# 03_Codec.net
KiCad netlist of a schematic drawn in Altium Designer
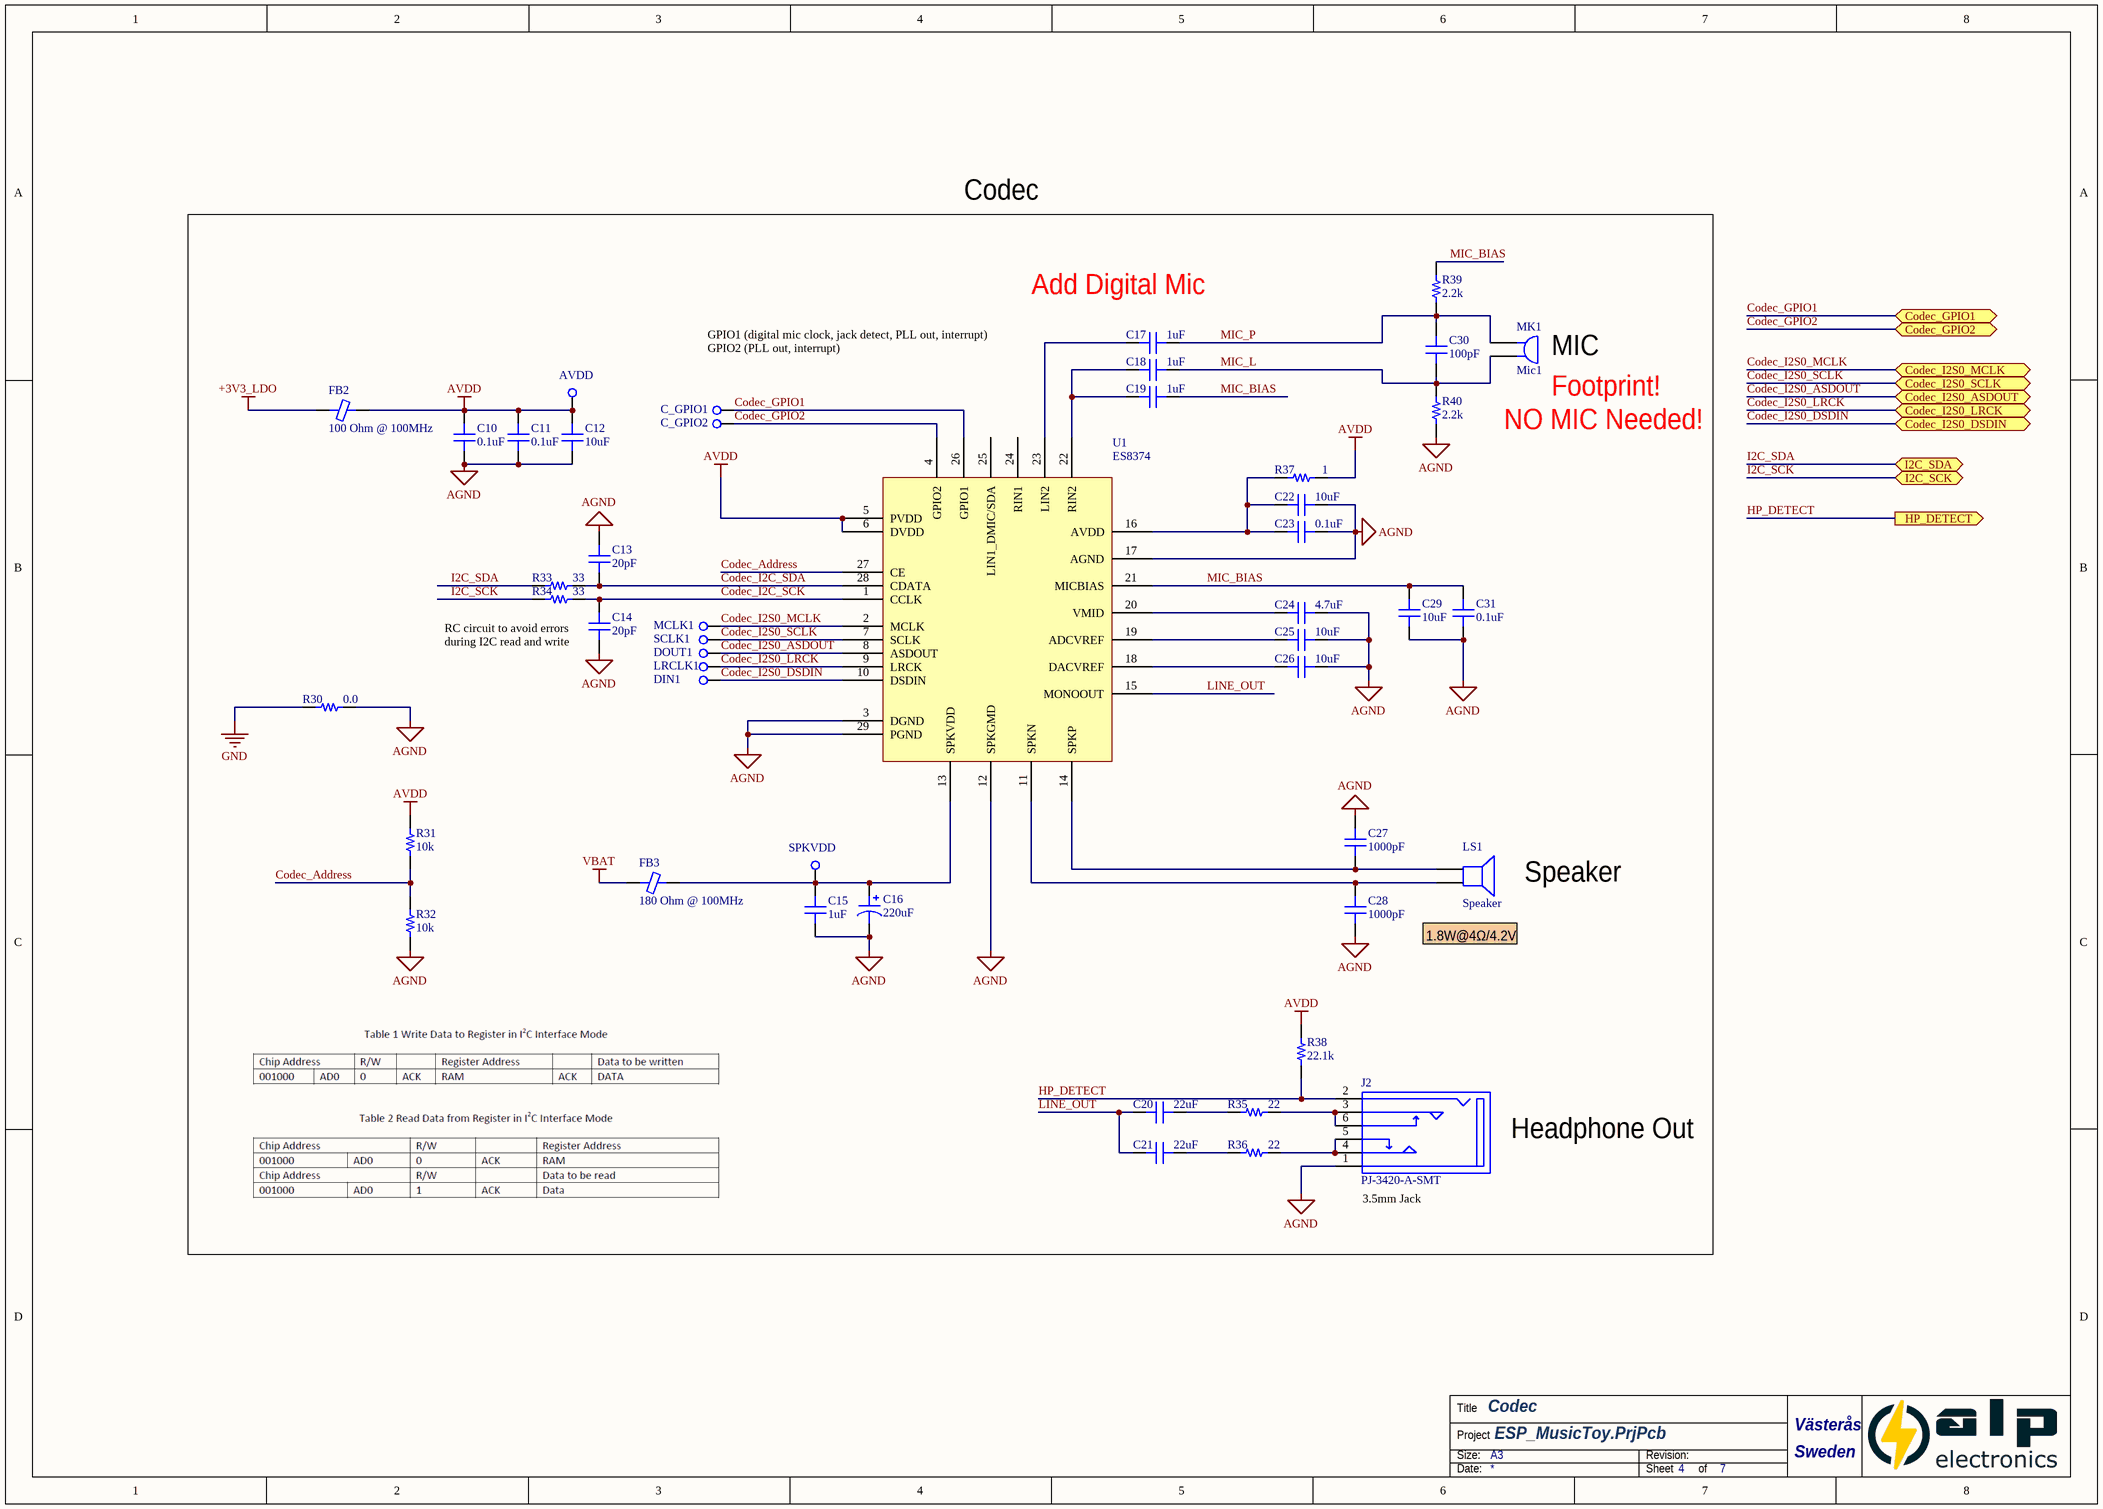
[diagram p0: [03] Codec.SchDoc]

(export (version "E")
  (design (tool "Eeschema 10.0.6"))
  (components
    (comp (ref "AVDD")
      (value "RCT-0C")
      (footprint "3D FootPrint_Backup:0.5mm-TestPad")
      (description "0805 PROBE PAD")
      (fields (field (name "MANUFACTURER") "TE Connectivity AMP Connectors"))
      (libsource (lib "Celestial Library Database") (part "Test Point"))
    )
    (comp (ref "C10")
      (value "0.1uF")
      (footprint "CAP 0603/1608")
      (description "CAP CER 0.1UF 16V X7R 0603")
      (fields (field (name "PART NUMBER") "CC0603KPX7R7BB104") (field (name "MANUFACTURER") "Yageo"))
      (libsource (lib "Celestial Library Database") (part "Capacitor"))
    )
    (comp (ref "C11")
      (value "0.1uF")
      (footprint "CAP 0603/1608")
      (description "CAP CER 0.1UF 16V X7R 0603")
      (fields (field (name "PART NUMBER") "CC0603KPX7R7BB104") (field (name "MANUFACTURER") "Yageo"))
      (libsource (lib "Celestial Library Database") (part "Capacitor"))
    )
    (comp (ref "C12")
      (value "10uF")
      (footprint "CAP 0603/1608")
      (description "CAP CER 10UF 10V X5R 0603")
      (fields
        (field (name "PART NUMBER") "C1608X5R1A106M080AC")
        (field (name "MANUFACTURER") "TDK Corporation")
      )
      (libsource (lib "Celestial Library Database") (part "Capacitor"))
    )
    (comp (ref "C13")
      (value "20pF")
      (footprint "CAP 0402/1005")
      (description "CAP CER 20PF 25V NP0 0402")
      (fields
        (field (name "PART NUMBER") "GRM1555C1E200JA01D")
        (field (name "MANUFACTURER") "Murata Electronics North America")
      )
      (libsource (lib "Celestial Library Database") (part "Capacitor"))
    )
    (comp (ref "C14")
      (value "20pF")
      (footprint "CAP 0402/1005")
      (description "CAP CER 20PF 25V NP0 0402")
      (fields
        (field (name "PART NUMBER") "GRM1555C1E200JA01D")
        (field (name "MANUFACTURER") "Murata Electronics North America")
      )
      (libsource (lib "Celestial Library Database") (part "Capacitor"))
    )
    (comp (ref "C15")
      (value "1uF")
      (footprint "CAP 0603/1608")
      (description "CAP CER 1UF 10V X7R 0603")
      (fields
        (field (name "PART NUMBER") "CGB3B1X7R1A105K055AC")
        (field (name "MANUFACTURER") "TDK Corporation")
      )
      (libsource (lib "Celestial Library Database") (part "Capacitor"))
    )
    (comp (ref "C16")
      (value "220uF")
      (footprint "CAP ALUM 6.6MM")
      (description "CAP ALUM 220UF 20% 16V SMD")
      (fields
        (field (name "PART NUMBER") "EEE-1CA221XP")
        (field (name "MANUFACTURER") "Panasonic Electronic Components")
      )
      (libsource (lib "Celestial Library Database") (part "Polarised Capacitor"))
    )
    (comp (ref "C17")
      (value "1uF")
      (footprint "CAP 0603/1608")
      (description "CAP CER 1UF 10V X7R 0603")
      (fields
        (field (name "PART NUMBER") "CGB3B1X7R1A105K055AC")
        (field (name "MANUFACTURER") "TDK Corporation")
      )
      (libsource (lib "Celestial Library Database") (part "Capacitor"))
    )
    (comp (ref "C18")
      (value "1uF")
      (footprint "CAP 0603/1608")
      (description "CAP CER 1UF 10V X7R 0603")
      (fields
        (field (name "PART NUMBER") "CGB3B1X7R1A105K055AC")
        (field (name "MANUFACTURER") "TDK Corporation")
      )
      (libsource (lib "Celestial Library Database") (part "Capacitor"))
    )
    (comp (ref "C19")
      (value "1uF")
      (footprint "CAP 0603/1608")
      (description "CAP CER 1UF 10V X7R 0603")
      (fields
        (field (name "PART NUMBER") "CGB3B1X7R1A105K055AC")
        (field (name "MANUFACTURER") "TDK Corporation")
      )
      (libsource (lib "Celestial Library Database") (part "Capacitor"))
    )
    (comp (ref "C20")
      (value "22uF")
      (footprint "CAP 0603/1608")
      (description "CAP CER 22UF 10V X5R 0603")
      (fields
        (field (name "PART NUMBER") "C1608X5R1A226M080AC")
        (field (name "MANUFACTURER") "TDK Corporation")
      )
      (libsource (lib "Celestial Library Database") (part "Capacitor"))
    )
    (comp (ref "C21")
      (value "22uF")
      (footprint "CAP 0603/1608")
      (description "CAP CER 22UF 10V X5R 0603")
      (fields
        (field (name "PART NUMBER") "C1608X5R1A226M080AC")
        (field (name "MANUFACTURER") "TDK Corporation")
      )
      (libsource (lib "Celestial Library Database") (part "Capacitor"))
    )
    (comp (ref "C22")
      (value "10uF")
      (footprint "CAP 0603/1608")
      (description "CAP CER 10UF 10V X5R 0603")
      (fields
        (field (name "PART NUMBER") "C1608X5R1A106M080AC")
        (field (name "MANUFACTURER") "TDK Corporation")
      )
      (libsource (lib "Celestial Library Database") (part "Capacitor"))
    )
    (comp (ref "C23")
      (value "0.1uF")
      (footprint "CAP 0603/1608")
      (description "CAP CER 0.1UF 16V X7R 0603")
      (fields (field (name "PART NUMBER") "CC0603KPX7R7BB104") (field (name "MANUFACTURER") "Yageo"))
      (libsource (lib "Celestial Library Database") (part "Capacitor"))
    )
    (comp (ref "C24")
      (value "4.7uF")
      (footprint "CAP 0603/1608")
      (description "CAP CER 4.7UF 10V X5R 0603")
      (fields
        (field (name "PART NUMBER") "C1608X5R1A475K080AC")
        (field (name "MANUFACTURER") "TDK Corporation")
      )
      (libsource (lib "Celestial Library Database") (part "Capacitor"))
    )
    (comp (ref "C25")
      (value "10uF")
      (footprint "CAP 0603/1608")
      (description "CAP CER 10UF 10V X5R 0603")
      (fields
        (field (name "PART NUMBER") "C1608X5R1A106M080AC")
        (field (name "MANUFACTURER") "TDK Corporation")
      )
      (libsource (lib "Celestial Library Database") (part "Capacitor"))
    )
    (comp (ref "C26")
      (value "10uF")
      (footprint "CAP 0603/1608")
      (description "CAP CER 10UF 10V X5R 0603")
      (fields
        (field (name "PART NUMBER") "C1608X5R1A106M080AC")
        (field (name "MANUFACTURER") "TDK Corporation")
      )
      (libsource (lib "Celestial Library Database") (part "Capacitor"))
    )
    (comp (ref "C27")
      (value "1000pF")
      (footprint "CAP 0603/1608")
      (description "CAP CER 1000PF 25V X7R 0603")
      (fields (field (name "PART NUMBER") "C0603C102K3RACTU") (field (name "MANUFACTURER") "Kemet"))
      (libsource (lib "Celestial Library Database") (part "Capacitor"))
    )
    (comp (ref "C28")
      (value "1000pF")
      (footprint "CAP 0603/1608")
      (description "CAP CER 1000PF 25V X7R 0603")
      (fields (field (name "PART NUMBER") "C0603C102K3RACTU") (field (name "MANUFACTURER") "Kemet"))
      (libsource (lib "Celestial Library Database") (part "Capacitor"))
    )
    (comp (ref "C29")
      (value "10uF")
      (footprint "CAP 0603/1608")
      (description "CAP CER 10UF 10V X5R 0603")
      (fields
        (field (name "PART NUMBER") "C1608X5R1A106M080AC")
        (field (name "MANUFACTURER") "TDK Corporation")
      )
      (libsource (lib "Celestial Library Database") (part "Capacitor"))
    )
    (comp (ref "C30")
      (value "100pF")
      (footprint "CAP 0402/1005")
      (description "CAP CER 100PF 25V NP0 0402")
      (fields (field (name "PART NUMBER") "C0402C101J3GACTU") (field (name "MANUFACTURER") "Kemet"))
      (libsource (lib "Celestial Library Database") (part "Capacitor"))
    )
    (comp (ref "C31")
      (value "0.1uF")
      (footprint "CAP 0603/1608")
      (description "CAP CER 0.1UF 16V X7R 0603")
      (fields (field (name "PART NUMBER") "CC0603KPX7R7BB104") (field (name "MANUFACTURER") "Yageo"))
      (libsource (lib "Celestial Library Database") (part "Capacitor"))
    )
    (comp (ref "C_GPIO1")
      (value "RCT-0C")
      (footprint "3D FootPrint_Backup:0.5mm-TestPad")
      (description "0805 PROBE PAD")
      (fields (field (name "MANUFACTURER") "TE Connectivity AMP Connectors"))
      (libsource (lib "Celestial Library Database") (part "Test Point"))
    )
    (comp (ref "C_GPIO2")
      (value "RCT-0C")
      (footprint "3D FootPrint_Backup:0.5mm-TestPad")
      (description "0805 PROBE PAD")
      (fields (field (name "MANUFACTURER") "TE Connectivity AMP Connectors"))
      (libsource (lib "Celestial Library Database") (part "Test Point"))
    )
    (comp (ref "DIN1")
      (value "RCT-0C")
      (footprint "3D FootPrint_Backup:0.5mm-TestPad")
      (description "0805 PROBE PAD")
      (fields (field (name "MANUFACTURER") "TE Connectivity AMP Connectors"))
      (libsource (lib "Celestial Library Database") (part "Test Point"))
    )
    (comp (ref "DOUT1")
      (value "RCT-0C")
      (footprint "3D FootPrint_Backup:0.5mm-TestPad")
      (description "0805 PROBE PAD")
      (fields (field (name "MANUFACTURER") "TE Connectivity AMP Connectors"))
      (libsource (lib "Celestial Library Database") (part "Test Point"))
    )
    (comp (ref "FB2")
      (value "100 Ohm @ 100MHz")
      (footprint "FER 0805/2012")
      (description "FERRITE CHIP 100 OHM 2000MA 0805")
      (fields
        (field (name "PART NUMBER") "CIC21P101NE")
        (field (name "MANUFACTURER") "Samsung Electro-Mechanics America, Inc.")
      )
      (libsource (lib "Celestial Library Database") (part "Ferrite Chip"))
    )
    (comp (ref "FB3")
      (value "180 Ohm @ 100MHz")
      (footprint "FER 0805/2012")
      (description "FERRITE CHIP 180 OHM 600MA 0805")
      (fields (field (name "PART NUMBER") "MMZ2012S181AT000") (field (name "MANUFACTURER") "TDK Corporation"))
      (libsource (lib "Celestial Library Database") (part "Ferrite Chip"))
    )
    (comp (ref "J2")
      (value "PJ-3420-A-SMT")
      (footprint "3D FootPrint_Backup:PJ-3420-A-SMT")
      (libsource (lib "Altium Component") (part "PJ-3420-A-SMT"))
    )
    (comp (ref "LRCLK1")
      (value "RCT-0C")
      (footprint "3D FootPrint_Backup:0.5mm-TestPad")
      (description "0805 PROBE PAD")
      (fields (field (name "MANUFACTURER") "TE Connectivity AMP Connectors"))
      (libsource (lib "Celestial Library Database") (part "Test Point"))
    )
    (comp (ref "LS1")
      (value "Speaker")
      (footprint "Connectors:JST XH B2B-XH-A")
      (description "Loudspeaker")
      (fields (field (name "PUBLISHER") "Altium Limited"))
      (libsource (lib "Miscellaneous Devices") (part "Speaker"))
    )
    (comp (ref "MCLK1")
      (value "RCT-0C")
      (footprint "3D FootPrint_Backup:0.5mm-TestPad")
      (description "0805 PROBE PAD")
      (fields (field (name "MANUFACTURER") "TE Connectivity AMP Connectors"))
      (libsource (lib "Celestial Library Database") (part "Test Point"))
    )
    (comp (ref "MK1")
      (value "Mic1")
      (footprint "Miscellaneous Connectors:HDR1X2")
      (description "Microphone")
      (fields (field (name "PUBLISHER") "Altium Limited"))
      (libsource (lib "Miscellaneous Devices") (part "Mic1"))
    )
    (comp (ref "R30")
      (value "0.0")
      (footprint "RES 0805/2012")
      (description "RES SMD 0.0 OHM JUMPER 1/8W 0805")
      (fields (field (name "PART NUMBER") "CR0805-J/-000ELF") (field (name "MANUFACTURER") "Bourns Inc."))
      (libsource (lib "Celestial Library Database") (part "Resistor"))
    )
    (comp (ref "R31")
      (value "10k")
      (footprint "RES 0402/1005")
      (description "RES SMD 10K OHM 5% 1/16W 0402")
      (fields (field (name "PART NUMBER") "RC0402JR-0710KL") (field (name "MANUFACTURER") "Yageo"))
      (libsource (lib "Celestial Library Database") (part "Resistor"))
    )
    (comp (ref "R32")
      (value "10k")
      (footprint "RES 0402/1005")
      (description "RES SMD 10K OHM 5% 1/16W 0402")
      (fields (field (name "PART NUMBER") "RC0402JR-0710KL") (field (name "MANUFACTURER") "Yageo"))
      (libsource (lib "Celestial Library Database") (part "Resistor"))
    )
    (comp (ref "R33")
      (value "33")
      (footprint "RES 0402/1005")
      (description "RES SMD 33 OHM 5% 1/10W 0402")
      (fields
        (field (name "PART NUMBER") "ERJ-2GEJ330X")
        (field (name "MANUFACTURER") "Panasonic Electronic Components")
      )
      (libsource (lib "Celestial Library Database") (part "Resistor"))
    )
    (comp (ref "R34")
      (value "33")
      (footprint "RES 0402/1005")
      (description "RES SMD 33 OHM 5% 1/10W 0402")
      (fields
        (field (name "PART NUMBER") "ERJ-2GEJ330X")
        (field (name "MANUFACTURER") "Panasonic Electronic Components")
      )
      (libsource (lib "Celestial Library Database") (part "Resistor"))
    )
    (comp (ref "R35")
      (value "22")
      (footprint "RES 0603/1608")
      (description "RES SMD 22 OHM 5% 1/10W 0603")
      (fields
        (field (name "PART NUMBER") "ERJ-3GEYJ220V")
        (field (name "MANUFACTURER") "Panasonic Electronic Components")
      )
      (libsource (lib "Celestial Library Database") (part "Resistor"))
    )
    (comp (ref "R36")
      (value "22")
      (footprint "RES 0603/1608")
      (description "RES SMD 22 OHM 5% 1/10W 0603")
      (fields
        (field (name "PART NUMBER") "ERJ-3GEYJ220V")
        (field (name "MANUFACTURER") "Panasonic Electronic Components")
      )
      (libsource (lib "Celestial Library Database") (part "Resistor"))
    )
    (comp (ref "R37")
      (value "1")
      (footprint "RES 0603/1608")
      (description "RES SMD 1 OHM 5% 1/10W 0603")
      (fields
        (field (name "PART NUMBER") "ERJ-3GEYJ1R0V")
        (field (name "MANUFACTURER") "Panasonic Electronic Components")
      )
      (libsource (lib "Celestial Library Database") (part "Resistor"))
    )
    (comp (ref "R38")
      (value "22.1k")
      (footprint "RES 0402/1005")
      (description "RES SMD 22.1K OHM 1% 1/10W 0402")
      (fields
        (field (name "PART NUMBER") "ERJ-2RKF2212X")
        (field (name "MANUFACTURER") "Panasonic Electronic Components")
      )
      (libsource (lib "Celestial Library Database") (part "Resistor"))
    )
    (comp (ref "R39")
      (value "2.2k")
      (footprint "RES 0402/1005")
      (description "RES SMD 2.2K OHM 5% 1/16W 0402")
      (fields (field (name "PART NUMBER") "RC0402JR-072K2L") (field (name "MANUFACTURER") "Yageo"))
      (libsource (lib "Celestial Library Database") (part "Resistor"))
    )
    (comp (ref "R40")
      (value "2.2k")
      (footprint "RES 0402/1005")
      (description "RES SMD 2.2K OHM 5% 1/16W 0402")
      (fields (field (name "PART NUMBER") "RC0402JR-072K2L") (field (name "MANUFACTURER") "Yageo"))
      (libsource (lib "Celestial Library Database") (part "Resistor"))
    )
    (comp (ref "SCLK1")
      (value "RCT-0C")
      (footprint "3D FootPrint_Backup:0.5mm-TestPad")
      (description "0805 PROBE PAD")
      (fields (field (name "MANUFACTURER") "TE Connectivity AMP Connectors"))
      (libsource (lib "Celestial Library Database") (part "Test Point"))
    )
    (comp (ref "SPKVDD")
      (value "RCT-0C")
      (footprint "3D FootPrint_Backup:0.5mm-TestPad")
      (description "0805 PROBE PAD")
      (fields (field (name "MANUFACTURER") "TE Connectivity AMP Connectors"))
      (libsource (lib "Celestial Library Database") (part "Test Point"))
    )
    (comp (ref "U1")
      (value "ES8374")
      (footprint "QFN28 4x4mm 0.4mm Pitch")
      (description "IC AMP AUDIO CODEC  1.8W QFN28")
      (fields (field (name "MANUFACTURER") "Evereset Semi"))
      (libsource (lib "Celestial Library Database") (part "ES8374"))
    )
  )
  (nets
    (net (code "1") (name "+3V3_LDO") (class "Default")
      (node (ref "FB2") (pin "1") (pinfunction "1_1") (pintype "passive"))
    )
    (net (code "2") (name "/Codec_Address") (class "Default")
      (node (ref "R31") (pin "1") (pinfunction "1_1") (pintype "passive"))
      (node (ref "R32") (pin "2") (pinfunction "2_2") (pintype "passive"))
      (node (ref "U1") (pin "27") (pinfunction "CE_27") (pintype "passive"))
    )
    (net (code "3") (name "/Codec_GPIO1") (class "Default")
      (node (ref "C_GPIO1") (pin "1") (pinfunction "TP_1") (pintype "passive"))
      (node (ref "U1") (pin "26") (pinfunction "GPIO1_26") (pintype "passive"))
    )
    (net (code "4") (name "/Codec_GPIO2") (class "Default")
      (node (ref "C_GPIO2") (pin "1") (pinfunction "TP_1") (pintype "passive"))
      (node (ref "U1") (pin "4") (pinfunction "GPIO2_4") (pintype "passive"))
    )
    (net (code "5") (name "/Codec_I2C_SCK") (class "Default")
      (node (ref "C14") (pin "2") (pinfunction "2_2") (pintype "passive"))
      (node (ref "R34") (pin "2") (pinfunction "2_2") (pintype "passive"))
      (node (ref "U1") (pin "1") (pinfunction "CCLK_1") (pintype "passive"))
    )
    (net (code "6") (name "/Codec_I2C_SDA") (class "Default")
      (node (ref "C13") (pin "1") (pinfunction "1_1") (pintype "passive"))
      (node (ref "R33") (pin "2") (pinfunction "2_2") (pintype "passive"))
      (node (ref "U1") (pin "28") (pinfunction "CDATA_28") (pintype "passive"))
    )
    (net (code "7") (name "/Codec_I2S0_ASDOUT") (class "Default")
      (node (ref "DOUT1") (pin "1") (pinfunction "TP_1") (pintype "passive"))
      (node (ref "U1") (pin "8") (pinfunction "ASDOUT_8") (pintype "passive"))
    )
    (net (code "8") (name "/Codec_I2S0_DSDIN") (class "Default")
      (node (ref "DIN1") (pin "1") (pinfunction "TP_1") (pintype "passive"))
      (node (ref "U1") (pin "10") (pinfunction "DSDIN_10") (pintype "passive"))
    )
    (net (code "9") (name "/Codec_I2S0_LRCK") (class "Default")
      (node (ref "LRCLK1") (pin "1") (pinfunction "TP_1") (pintype "passive"))
      (node (ref "U1") (pin "9") (pinfunction "LRCK_9") (pintype "passive"))
    )
    (net (code "10") (name "/Codec_I2S0_MCLK") (class "Default")
      (node (ref "MCLK1") (pin "1") (pinfunction "TP_1") (pintype "passive"))
      (node (ref "U1") (pin "2") (pinfunction "MCLK_2") (pintype "passive"))
    )
    (net (code "11") (name "/Codec_I2S0_SCLK") (class "Default")
      (node (ref "SCLK1") (pin "1") (pinfunction "TP_1") (pintype "passive"))
      (node (ref "U1") (pin "7") (pinfunction "SCLK_7") (pintype "passive"))
    )
    (net (code "12") (name "/HP_DETECT") (class "Default")
      (node (ref "J2") (pin "2") (pinfunction "2_2") (pintype "passive"))
      (node (ref "R38") (pin "1") (pinfunction "1_1") (pintype "passive"))
    )
    (net (code "13") (name "/I2C_SCK") (class "Default")
      (node (ref "R34") (pin "1") (pinfunction "1_1") (pintype "passive"))
    )
    (net (code "14") (name "/I2C_SDA") (class "Default")
      (node (ref "R33") (pin "1") (pinfunction "1_1") (pintype "passive"))
    )
    (net (code "15") (name "/LINE_OUT") (class "Default")
      (node (ref "C20") (pin "1") (pinfunction "1_1") (pintype "passive"))
      (node (ref "C21") (pin "1") (pinfunction "1_1") (pintype "passive"))
      (node (ref "U1") (pin "15") (pinfunction "MONOOUT_15") (pintype "passive"))
    )
    (net (code "16") (name "/MIC_BIAS") (class "Default")
      (node (ref "C19") (pin "1") (pinfunction "1_1") (pintype "passive"))
      (node (ref "C29") (pin "2") (pinfunction "2_2") (pintype "passive"))
      (node (ref "C31") (pin "2") (pinfunction "2_2") (pintype "passive"))
      (node (ref "R39") (pin "2") (pinfunction "2_2") (pintype "passive"))
      (node (ref "U1") (pin "21") (pinfunction "MICBIAS_21") (pintype "passive"))
    )
    (net (code "17") (name "/MIC_L") (class "Default")
      (node (ref "C18") (pin "1") (pinfunction "1_1") (pintype "passive"))
      (node (ref "C30") (pin "1") (pinfunction "1_1") (pintype "passive"))
      (node (ref "MK1") (pin "2") (pinfunction "2_2") (pintype "passive"))
      (node (ref "R40") (pin "2") (pinfunction "2_2") (pintype "passive"))
    )
    (net (code "18") (name "/MIC_P") (class "Default")
      (node (ref "C17") (pin "1") (pinfunction "1_1") (pintype "passive"))
      (node (ref "C30") (pin "2") (pinfunction "2_2") (pintype "passive"))
      (node (ref "MK1") (pin "1") (pinfunction "1_1") (pintype "passive"))
      (node (ref "R39") (pin "1") (pinfunction "1_1") (pintype "passive"))
    )
    (net (code "19") (name "AGND") (class "Default")
      (node (ref "C10") (pin "1") (pinfunction "1_1") (pintype "passive"))
      (node (ref "C11") (pin "1") (pinfunction "1_1") (pintype "passive"))
      (node (ref "C12") (pin "1") (pinfunction "1_1") (pintype "passive"))
      (node (ref "C13") (pin "2") (pinfunction "2_2") (pintype "passive"))
      (node (ref "C14") (pin "1") (pinfunction "1_1") (pintype "passive"))
      (node (ref "C15") (pin "2") (pinfunction "2_2") (pintype "passive"))
      (node (ref "C16") (pin "2") (pinfunction "2_2") (pintype "passive"))
      (node (ref "C22") (pin "2") (pinfunction "2_2") (pintype "passive"))
      (node (ref "C23") (pin "1") (pinfunction "1_1") (pintype "passive"))
      (node (ref "C24") (pin "2") (pinfunction "2_2") (pintype "passive"))
      (node (ref "C25") (pin "2") (pinfunction "2_2") (pintype "passive"))
      (node (ref "C26") (pin "2") (pinfunction "2_2") (pintype "passive"))
      (node (ref "C27") (pin "2") (pinfunction "2_2") (pintype "passive"))
      (node (ref "C28") (pin "1") (pinfunction "1_1") (pintype "passive"))
      (node (ref "C29") (pin "1") (pinfunction "1_1") (pintype "passive"))
      (node (ref "C31") (pin "1") (pinfunction "1_1") (pintype "passive"))
      (node (ref "J2") (pin "1") (pinfunction "1_1") (pintype "passive"))
      (node (ref "R30") (pin "2") (pinfunction "2_2") (pintype "passive"))
      (node (ref "R32") (pin "1") (pinfunction "1_1") (pintype "passive"))
      (node (ref "R40") (pin "1") (pinfunction "1_1") (pintype "passive"))
      (node (ref "U1") (pin "12") (pinfunction "SPKGMD_12") (pintype "passive"))
      (node (ref "U1") (pin "17") (pinfunction "AGND_17") (pintype "passive"))
      (node (ref "U1") (pin "29") (pinfunction "PGND_29") (pintype "passive"))
      (node (ref "U1") (pin "3") (pinfunction "DGND_3") (pintype "passive"))
    )
    (net (code "20") (name "AVDD") (class "Default")
      (node (ref "AVDD") (pin "1") (pinfunction "TP_1") (pintype "passive"))
      (node (ref "C10") (pin "2") (pinfunction "2_2") (pintype "passive"))
      (node (ref "C11") (pin "2") (pinfunction "2_2") (pintype "passive"))
      (node (ref "C12") (pin "2") (pinfunction "2_2") (pintype "passive"))
      (node (ref "FB2") (pin "2") (pinfunction "2_2") (pintype "passive"))
      (node (ref "R31") (pin "2") (pinfunction "2_2") (pintype "passive"))
      (node (ref "R37") (pin "1") (pinfunction "1_1") (pintype "passive"))
      (node (ref "R38") (pin "2") (pinfunction "2_2") (pintype "passive"))
      (node (ref "U1") (pin "5") (pinfunction "PVDD_5") (pintype "passive"))
      (node (ref "U1") (pin "6") (pinfunction "DVDD_6") (pintype "passive"))
    )
    (net (code "21") (name "GND") (class "Default")
      (node (ref "R30") (pin "1") (pinfunction "1_1") (pintype "passive"))
    )
    (net (code "22") (name "Net-(C20-Pad2)") (class "Default")
      (node (ref "C20") (pin "2") (pinfunction "2_2") (pintype "passive"))
      (node (ref "R35") (pin "1") (pinfunction "1_1") (pintype "passive"))
    )
    (net (code "23") (name "Net-(C21-Pad2)") (class "Default")
      (node (ref "C21") (pin "2") (pinfunction "2_2") (pintype "passive"))
      (node (ref "R36") (pin "1") (pinfunction "1_1") (pintype "passive"))
    )
    (net (code "24") (name "Net-(J2-Pad3)") (class "Default")
      (node (ref "J2") (pin "3") (pinfunction "3_3") (pintype "passive"))
      (node (ref "J2") (pin "6") (pinfunction "6_6") (pintype "passive"))
      (node (ref "R35") (pin "2") (pinfunction "2_2") (pintype "passive"))
    )
    (net (code "25") (name "Net-(J2-Pad4)") (class "Default")
      (node (ref "J2") (pin "4") (pinfunction "4_4") (pintype "passive"))
      (node (ref "J2") (pin "5") (pinfunction "5_5") (pintype "passive"))
      (node (ref "R36") (pin "2") (pinfunction "2_2") (pintype "passive"))
    )
    (net (code "26") (name "Net-(SPKVDD-TP)") (class "Default")
      (node (ref "C15") (pin "1") (pinfunction "1_1") (pintype "passive"))
      (node (ref "C16") (pin "1") (pinfunction "1_1") (pintype "passive"))
      (node (ref "FB3") (pin "2") (pinfunction "2_2") (pintype "passive"))
      (node (ref "SPKVDD") (pin "1") (pinfunction "TP_1") (pintype "passive"))
      (node (ref "U1") (pin "13") (pinfunction "SPKVDD_13") (pintype "passive"))
    )
    (net (code "27") (name "Net-(U1-ADCVREF)") (class "Default")
      (node (ref "C25") (pin "1") (pinfunction "1_1") (pintype "passive"))
      (node (ref "U1") (pin "19") (pinfunction "ADCVREF_19") (pintype "passive"))
    )
    (net (code "28") (name "Net-(U1-AVDD)") (class "Default")
      (node (ref "C22") (pin "1") (pinfunction "1_1") (pintype "passive"))
      (node (ref "C23") (pin "2") (pinfunction "2_2") (pintype "passive"))
      (node (ref "R37") (pin "2") (pinfunction "2_2") (pintype "passive"))
      (node (ref "U1") (pin "16") (pinfunction "AVDD_16") (pintype "passive"))
    )
    (net (code "29") (name "Net-(U1-DACVREF)") (class "Default")
      (node (ref "C26") (pin "1") (pinfunction "1_1") (pintype "passive"))
      (node (ref "U1") (pin "18") (pinfunction "DACVREF_18") (pintype "passive"))
    )
    (net (code "30") (name "Net-(U1-LIN2)") (class "Default")
      (node (ref "C17") (pin "2") (pinfunction "2_2") (pintype "passive"))
      (node (ref "U1") (pin "23") (pinfunction "LIN2_23") (pintype "passive"))
    )
    (net (code "31") (name "Net-(U1-RIN2)") (class "Default")
      (node (ref "C18") (pin "2") (pinfunction "2_2") (pintype "passive"))
      (node (ref "C19") (pin "2") (pinfunction "2_2") (pintype "passive"))
      (node (ref "U1") (pin "22") (pinfunction "RIN2_22") (pintype "passive"))
    )
    (net (code "32") (name "Net-(U1-SPKN)") (class "Default")
      (node (ref "C28") (pin "2") (pinfunction "2_2") (pintype "passive"))
      (node (ref "LS1") (pin "2") (pinfunction "2_2") (pintype "passive"))
      (node (ref "U1") (pin "11") (pinfunction "SPKN_11") (pintype "passive"))
    )
    (net (code "33") (name "Net-(U1-SPKP)") (class "Default")
      (node (ref "C27") (pin "1") (pinfunction "1_1") (pintype "passive"))
      (node (ref "LS1") (pin "1") (pinfunction "1_1") (pintype "passive"))
      (node (ref "U1") (pin "14") (pinfunction "SPKP_14") (pintype "passive"))
    )
    (net (code "34") (name "Net-(U1-VMID)") (class "Default")
      (node (ref "C24") (pin "1") (pinfunction "1_1") (pintype "passive"))
      (node (ref "U1") (pin "20") (pinfunction "VMID_20") (pintype "passive"))
    )
    (net (code "35") (name "VBAT") (class "Default")
      (node (ref "FB3") (pin "1") (pinfunction "1_1") (pintype "passive"))
    )
    (net (code "36") (name "unconnected-(U1-LIN1_DMIC{slash}SDA-Pad25)") (class "Default")
      (node (ref "U1") (pin "25") (pinfunction "LIN1_DMIC/SDA_25") (pintype "passive"))
    )
    (net (code "37") (name "unconnected-(U1-RIN1-Pad24)") (class "Default")
      (node (ref "U1") (pin "24") (pinfunction "RIN1_24") (pintype "passive"))
    )
  )
)
